# Power.net
KiCad netlist of a schematic drawn in Altium Designer
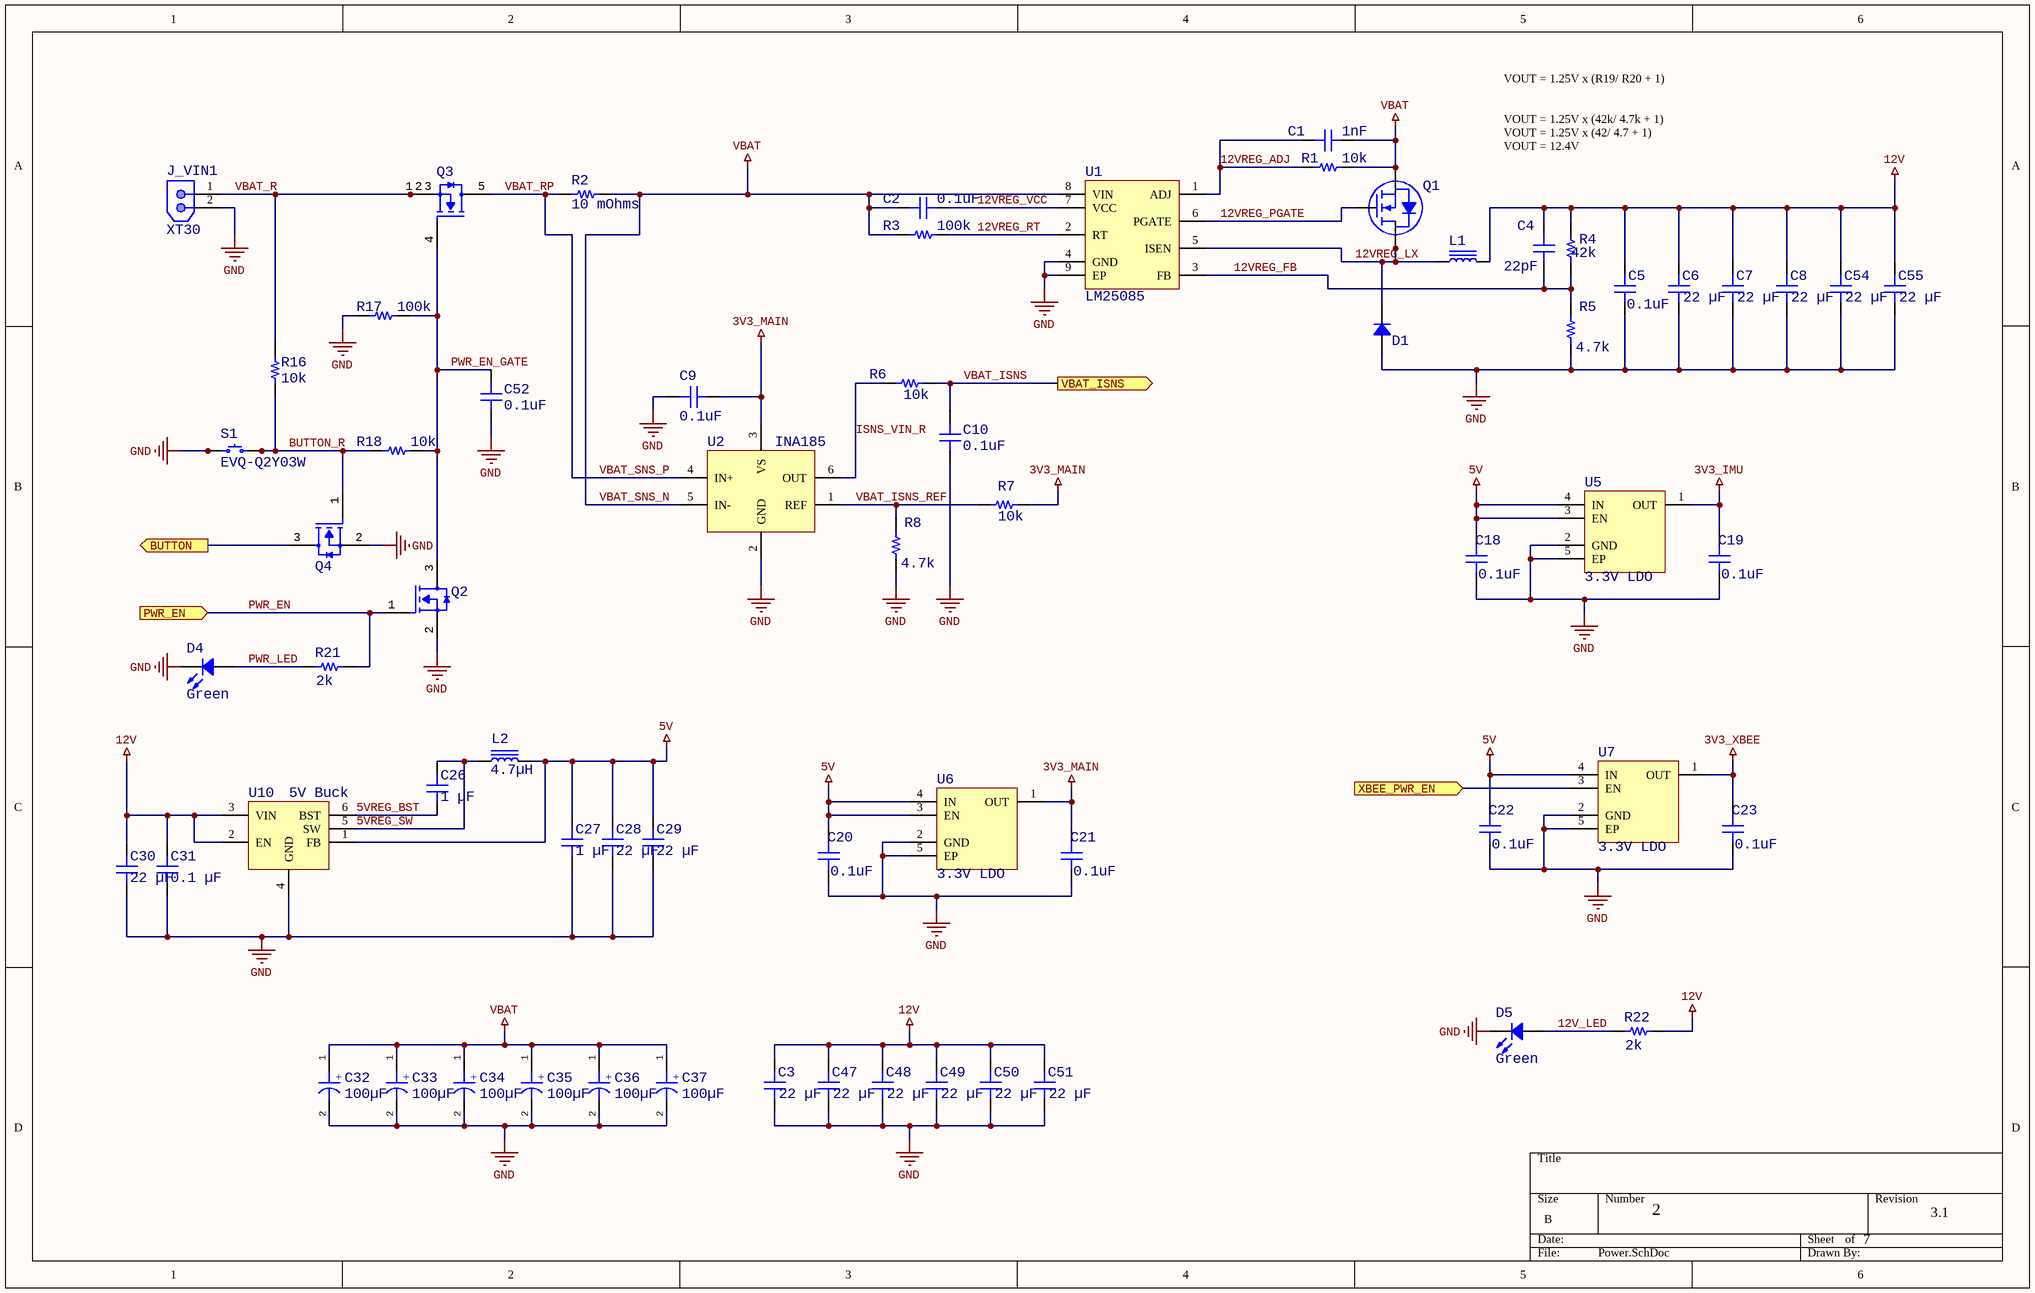
[diagram p0: Power.SchDoc]

(export (version "E")
  (design (tool "Eeschema 10.0.6"))
  (components
    (comp (ref "C1")
      (value "1nF")
      (footprint "CAP_0402")
      (description "CAP CER 402")
      (libsource (lib "IC") (part "CAP_0402"))
    )
    (comp (ref "C2")
      (value "0.1uF")
      (footprint "CAP_0402")
      (description "CAP CER 402")
      (libsource (lib "IC") (part "CAP_0402"))
    )
    (comp (ref "C3")
      (value "22 µF")
      (footprint "CAP 0805_2012")
      (description "CAP CER 22UF 16V X6S 0805")
      (fields (field (name "PART NUMBER") "KGM21AS61C226MU") (field (name "MANUFACTURER") "KYOCERA AVX"))
      (libsource (lib "Celestial Altium Library - altium_library") (part "Capacitor"))
    )
    (comp (ref "C4")
      (value "22pF")
      (footprint "CAP_0402")
      (description "CAP CER 402")
      (libsource (lib "IC") (part "CAP_0402"))
    )
    (comp (ref "C5")
      (value "0.1uF")
      (footprint "CAP_0402")
      (description "CAP CER 402")
      (libsource (lib "IC") (part "CAP_0402"))
    )
    (comp (ref "C6")
      (value "22 µF")
      (footprint "CAP 0805_2012")
      (description "CAP CER 22UF 16V X6S 0805")
      (fields (field (name "PART NUMBER") "KGM21AS61C226MU") (field (name "MANUFACTURER") "KYOCERA AVX"))
      (libsource (lib "Celestial Altium Library - altium_library") (part "Capacitor"))
    )
    (comp (ref "C7")
      (value "22 µF")
      (footprint "CAP 0805_2012")
      (description "CAP CER 22UF 16V X6S 0805")
      (fields (field (name "PART NUMBER") "KGM21AS61C226MU") (field (name "MANUFACTURER") "KYOCERA AVX"))
      (libsource (lib "Celestial Altium Library - altium_library") (part "Capacitor"))
    )
    (comp (ref "C8")
      (value "22 µF")
      (footprint "CAP 0805_2012")
      (description "CAP CER 22UF 16V X6S 0805")
      (fields (field (name "PART NUMBER") "KGM21AS61C226MU") (field (name "MANUFACTURER") "KYOCERA AVX"))
      (libsource (lib "Celestial Altium Library - altium_library") (part "Capacitor"))
    )
    (comp (ref "C9")
      (value "0.1uF")
      (footprint "CAP_0402")
      (description "CAP CER 402")
      (libsource (lib "IC") (part "CAP_0402"))
    )
    (comp (ref "C10")
      (value "0.1uF")
      (footprint "CAP_0402")
      (description "CAP CER 402")
      (libsource (lib "IC") (part "CAP_0402"))
    )
    (comp (ref "C18")
      (value "0.1uF")
      (footprint "CAP_0402")
      (description "CAP CER 402")
      (libsource (lib "IC") (part "CAP_0402"))
    )
    (comp (ref "C19")
      (value "0.1uF")
      (footprint "CAP_0402")
      (description "CAP CER 402")
      (libsource (lib "IC") (part "CAP_0402"))
    )
    (comp (ref "C20")
      (value "0.1uF")
      (footprint "CAP_0402")
      (description "CAP CER 402")
      (libsource (lib "IC") (part "CAP_0402"))
    )
    (comp (ref "C21")
      (value "0.1uF")
      (footprint "CAP_0402")
      (description "CAP CER 402")
      (libsource (lib "IC") (part "CAP_0402"))
    )
    (comp (ref "C22")
      (value "0.1uF")
      (footprint "CAP_0402")
      (description "CAP CER 402")
      (libsource (lib "IC") (part "CAP_0402"))
    )
    (comp (ref "C23")
      (value "0.1uF")
      (footprint "CAP_0402")
      (description "CAP CER 402")
      (libsource (lib "IC") (part "CAP_0402"))
    )
    (comp (ref "C26")
      (value "1 µF")
      (footprint "CAP 0402_1005")
      (description "CAP CER 0.1UF 16V X7R 0402")
      (fields (field (name "PART NUMBER") "C0402C104K4RACAUTO") (field (name "MANUFACTURER") "KEMET"))
      (libsource (lib "Celestial Altium Library - altium_library") (part "Capacitor"))
    )
    (comp (ref "C27")
      (value "1 µF")
      (footprint "CAP 0402_1005")
      (description "CAP CER 0.1UF 16V X7R 0402")
      (fields (field (name "PART NUMBER") "C0402C104K4RACAUTO") (field (name "MANUFACTURER") "KEMET"))
      (libsource (lib "Celestial Altium Library - altium_library") (part "Capacitor"))
    )
    (comp (ref "C28")
      (value "22 µF")
      (footprint "CAP 0603_1608")
      (description "CAP CER 47UF 6.3V X5R 0603")
      (fields
        (field (name "PART NUMBER") "C0603B476M007T")
        (field (name "MANUFACTURER") "Holy Stone Enterprise Co., Ltd.")
      )
      (libsource (lib "Celestial Altium Library - altium_library") (part "Capacitor"))
    )
    (comp (ref "C29")
      (value "22 µF")
      (footprint "CAP 0603_1608")
      (description "CAP CER 47UF 6.3V X5R 0603")
      (fields
        (field (name "PART NUMBER") "C0603B476M007T")
        (field (name "MANUFACTURER") "Holy Stone Enterprise Co., Ltd.")
      )
      (libsource (lib "Celestial Altium Library - altium_library") (part "Capacitor"))
    )
    (comp (ref "C30")
      (value "22 µF")
      (footprint "CAP 0603_1608")
      (description "CAP CER 47UF 6.3V X5R 0603")
      (fields
        (field (name "PART NUMBER") "C0603B476M007T")
        (field (name "MANUFACTURER") "Holy Stone Enterprise Co., Ltd.")
      )
      (libsource (lib "Celestial Altium Library - altium_library") (part "Capacitor"))
    )
    (comp (ref "C31")
      (value "0.1 µF")
      (footprint "CAP 0402_1005")
      (description "CAP CER 0.1UF 16V X7R 0402")
      (fields (field (name "PART NUMBER") "C0402C104K4RACAUTO") (field (name "MANUFACTURER") "KEMET"))
      (libsource (lib "Celestial Altium Library - altium_library") (part "Capacitor"))
    )
    (comp (ref "C32")
      (value "100µF")
      (footprint "UWZ1V101MCL1GS")
      (fields (field (name "Comment") "UWZ1V101MCL1GS"))
      (libsource (lib "Raise Robotics") (part "Polarized Capacitor Pin1+"))
    )
    (comp (ref "C33")
      (value "100µF")
      (footprint "UWZ1V101MCL1GS")
      (fields (field (name "Comment") "UWZ1V101MCL1GS"))
      (libsource (lib "Raise Robotics") (part "Polarized Capacitor Pin1+"))
    )
    (comp (ref "C34")
      (value "100µF")
      (footprint "UWZ1V101MCL1GS")
      (fields (field (name "Comment") "UWZ1V101MCL1GS"))
      (libsource (lib "Raise Robotics") (part "Polarized Capacitor Pin1+"))
    )
    (comp (ref "C35")
      (value "100µF")
      (footprint "UWZ1V101MCL1GS")
      (fields (field (name "Comment") "UWZ1V101MCL1GS"))
      (libsource (lib "Raise Robotics") (part "Polarized Capacitor Pin1+"))
    )
    (comp (ref "C36")
      (value "100µF")
      (footprint "UWZ1V101MCL1GS")
      (fields (field (name "Comment") "UWZ1V101MCL1GS"))
      (libsource (lib "Raise Robotics") (part "Polarized Capacitor Pin1+"))
    )
    (comp (ref "C37")
      (value "100µF")
      (footprint "UWZ1V101MCL1GS")
      (fields (field (name "Comment") "UWZ1V101MCL1GS"))
      (libsource (lib "Raise Robotics") (part "Polarized Capacitor Pin1+"))
    )
    (comp (ref "C47")
      (value "22 µF")
      (footprint "CAP 0805_2012")
      (description "CAP CER 22UF 16V X6S 0805")
      (fields (field (name "PART NUMBER") "KGM21AS61C226MU") (field (name "MANUFACTURER") "KYOCERA AVX"))
      (libsource (lib "Celestial Altium Library - altium_library") (part "Capacitor"))
    )
    (comp (ref "C48")
      (value "22 µF")
      (footprint "CAP 0805_2012")
      (description "CAP CER 22UF 16V X6S 0805")
      (fields (field (name "PART NUMBER") "KGM21AS61C226MU") (field (name "MANUFACTURER") "KYOCERA AVX"))
      (libsource (lib "Celestial Altium Library - altium_library") (part "Capacitor"))
    )
    (comp (ref "C49")
      (value "22 µF")
      (footprint "CAP 0805_2012")
      (description "CAP CER 22UF 16V X6S 0805")
      (fields (field (name "PART NUMBER") "KGM21AS61C226MU") (field (name "MANUFACTURER") "KYOCERA AVX"))
      (libsource (lib "Celestial Altium Library - altium_library") (part "Capacitor"))
    )
    (comp (ref "C50")
      (value "22 µF")
      (footprint "CAP 0805_2012")
      (description "CAP CER 22UF 16V X6S 0805")
      (fields (field (name "PART NUMBER") "KGM21AS61C226MU") (field (name "MANUFACTURER") "KYOCERA AVX"))
      (libsource (lib "Celestial Altium Library - altium_library") (part "Capacitor"))
    )
    (comp (ref "C51")
      (value "22 µF")
      (footprint "CAP 0805_2012")
      (description "CAP CER 22UF 16V X6S 0805")
      (fields (field (name "PART NUMBER") "KGM21AS61C226MU") (field (name "MANUFACTURER") "KYOCERA AVX"))
      (libsource (lib "Celestial Altium Library - altium_library") (part "Capacitor"))
    )
    (comp (ref "C52")
      (value "0.1uF")
      (footprint "CAP_0402")
      (description "CAP CER 402")
      (libsource (lib "IC") (part "CAP_0402"))
    )
    (comp (ref "C54")
      (value "22 µF")
      (footprint "CAP 0805_2012")
      (description "CAP CER 22UF 16V X6S 0805")
      (fields (field (name "PART NUMBER") "KGM21AS61C226MU") (field (name "MANUFACTURER") "KYOCERA AVX"))
      (libsource (lib "Celestial Altium Library - altium_library") (part "Capacitor"))
    )
    (comp (ref "C55")
      (value "22 µF")
      (footprint "CAP 0805_2012")
      (description "CAP CER 22UF 16V X6S 0805")
      (fields (field (name "PART NUMBER") "KGM21AS61C226MU") (field (name "MANUFACTURER") "KYOCERA AVX"))
      (libsource (lib "Celestial Altium Library - altium_library") (part "Capacitor"))
    )
    (comp (ref "D1")
      (value "SE10FGHM3/H")
      (footprint "SMF DO-219AB")
      (description "DIODE GEN PURP 400V 1A DO219AB")
      (fields (field (name "MANUFACTURER") "Vishay Semiconductor Diodes Division"))
      (libsource (lib "Celestial Altium Library - altium_library") (part "Diode"))
    )
    (comp (ref "D4")
      (value "Green")
      (footprint "LED 0603_1608 GREEN")
      (description "LED GREEN CLEAR 2SMD")
      (fields (field (name "PART NUMBER") "XZCDGK53W-8VF") (field (name "MANUFACTURER") "SunLED"))
      (libsource (lib "Celestial Altium Library - altium_library") (part "LED"))
    )
    (comp (ref "D5")
      (value "Green")
      (footprint "LED 0603_1608 GREEN")
      (description "LED GREEN CLEAR 2SMD")
      (fields (field (name "PART NUMBER") "XZCDGK53W-8VF") (field (name "MANUFACTURER") "SunLED"))
      (libsource (lib "Celestial Altium Library - altium_library") (part "LED"))
    )
    (comp (ref "J_VIN1") (value "XT30") (footprint "XT30") (libsource (lib "IC") (part "XT30")))
    (comp (ref "L1")
      (value "MPL-AL5050-5R6")
      (footprint "MPL-AL5050-5R6")
      (description "FIXED IND 5.6UH 6.8A 20 MOHM SMD")
      (fields (field (name "MF") "Laird-Signal Integrity Products") (field (name "MP") "MGV05021R0M-10"))
      (libsource (lib "IC") (part "MPL-AL5050-5R6"))
    )
    (comp (ref "L2")
      (value "4.7µH")
      (footprint "IND 1008_2520")
      (description "FIXED IND 4.7UH 1A 110 MOHM SMD")
      (fields (field (name "PART NUMBER") "MLP2520S4R7ST0S1") (field (name "MANUFACTURER") "TDK Corporation"))
      (libsource (lib "Celestial Altium Library - altium_library") (part "Inductor"))
    )
    (comp (ref "Q1")
      (value "NVTFS5C680NL")
      (footprint "NVTFS015N04CTAG")
      (description "N-FET")
      (libsource (lib "IC") (part "NVTFS5C680NL"))
    )
    (comp (ref "Q2")
      (value "DMN61D9UWQ-7")
      (footprint "DMN61D9UWQ-7")
      (description "Small Signal Field-Effect Transistor")
      (libsource (lib "Raise Robotics") (part "n-FET 3 pin SOT"))
    )
    (comp (ref "Q3")
      (value "STL220N6F7")
      (footprint "STL220N6F7")
      (fields (field (name "POWER") "4.8W"))
      (libsource (lib "Raise Robotics") (part "LFPAK56, Power-SO8"))
    )
    (comp (ref "Q4")
      (value "DMN61D9UWQ-7")
      (footprint "DMN61D9UWQ-7")
      (description "Small Signal Field-Effect Transistor")
      (libsource (lib "Raise Robotics") (part "n-FET 3 pin SOT"))
    )
    (comp (ref "R1")
      (value "10k")
      (footprint "RES_0402")
      (description "RES 0402")
      (libsource (lib "IC") (part "RES_0402"))
    )
    (comp (ref "R2")
      (value "10 mOhms")
      (footprint "RES 1206_3216")
      (description "RES 0.039 OHM 1% 3/4W 1206")
      (fields (field (name "PART NUMBER") "KRL1632E-M-R039-F-T5") (field (name "MANUFACTURER") "Susumu"))
      (libsource (lib "Celestial Altium Library - altium_library") (part "Resistor"))
    )
    (comp (ref "R3")
      (value "100k")
      (footprint "RES_0402")
      (description "RES 0402")
      (libsource (lib "IC") (part "RES_0402"))
    )
    (comp (ref "R4")
      (value "42k")
      (footprint "RES_0402")
      (description "RES 0402")
      (libsource (lib "IC") (part "RES_0402"))
    )
    (comp (ref "R5")
      (value "4.7k")
      (footprint "RES_0402")
      (description "RES 0402")
      (libsource (lib "IC") (part "RES_0402"))
    )
    (comp (ref "R6")
      (value "10k")
      (footprint "RES_0402")
      (description "RES 0402")
      (libsource (lib "IC") (part "RES_0402"))
    )
    (comp (ref "R7")
      (value "10k")
      (footprint "RES_0402")
      (description "RES 0402")
      (libsource (lib "IC") (part "RES_0402"))
    )
    (comp (ref "R8")
      (value "4.7k")
      (footprint "RES_0402")
      (description "RES 0402")
      (libsource (lib "IC") (part "RES_0402"))
    )
    (comp (ref "R16")
      (value "10k")
      (footprint "RES_0402")
      (description "RES 0402")
      (libsource (lib "IC") (part "RES_0402"))
    )
    (comp (ref "R17")
      (value "100k")
      (footprint "RES_0402")
      (description "RES 0402")
      (libsource (lib "IC") (part "RES_0402"))
    )
    (comp (ref "R18")
      (value "10k")
      (footprint "RES_0402")
      (description "RES 0402")
      (libsource (lib "IC") (part "RES_0402"))
    )
    (comp (ref "R21")
      (value "2k")
      (footprint "RES_0402")
      (description "RES 0402")
      (libsource (lib "IC") (part "RES_0402"))
    )
    (comp (ref "R22")
      (value "2k")
      (footprint "RES_0402")
      (description "RES 0402")
      (libsource (lib "IC") (part "RES_0402"))
    )
    (comp (ref "S1")
      (value "EVQ-Q2Y03W")
      (footprint "PANASONIC EVQQ2")
      (description "SWITCH TACTILE SPST-NO 0.02A 15V")
      (fields (field (name "MANUFACTURER") "Panasonic Electronic Components"))
      (libsource (lib "Celestial Altium Library - altium_library") (part "SPST-NO 4 PIN"))
    )
    (comp (ref "U1")
      (value "LM25085")
      (footprint "8-WSON_3x3_0.5mm")
      (description "PFET Buck Controller")
      (libsource (lib "IC") (part "LM25085"))
    )
    (comp (ref "U2")
      (value "INA185")
      (footprint "TI SC70-6 DCK")
      (description "INA185A2")
      (libsource (lib "IC") (part "INA185"))
    )
    (comp (ref "U5") (value "3.3V LDO") (footprint "XDFN-4") (libsource (lib "IC") (part "TLV74033PDQNR")))
    (comp (ref "U6") (value "3.3V LDO") (footprint "XDFN-4") (libsource (lib "IC") (part "TLV74033PDQNR")))
    (comp (ref "U7") (value "3.3V LDO") (footprint "XDFN-4") (libsource (lib "IC") (part "TLV74033PDQNR")))
    (comp (ref "U10")
      (value "5V Buck")
      (footprint "TSOT-26-6 - 3.2mm")
      (description "5V fixed step down Buck")
      (libsource (lib "IC") (part "AP63205WU-7"))
    )
  )
  (nets
    (net (code "1") (name "/5VREG_BST") (class "Default")
      (node (ref "C26") (pin "1") (pinfunction "1_1") (pintype "passive"))
      (node (ref "U10") (pin "6") (pinfunction "BST_6") (pintype "passive"))
    )
    (net (code "2") (name "/5VREG_SW") (class "Default")
      (node (ref "C26") (pin "2") (pinfunction "2_2") (pintype "passive"))
      (node (ref "L2") (pin "1") (pinfunction "1_1") (pintype "passive"))
      (node (ref "U10") (pin "5") (pinfunction "SW_5") (pintype "passive"))
    )
    (net (code "3") (name "/12VREG_ADJ") (class "Default")
      (node (ref "C1") (pin "1") (pinfunction "1_1") (pintype "passive"))
      (node (ref "R1") (pin "2") (pinfunction "2_2") (pintype "passive"))
      (node (ref "U1") (pin "1") (pinfunction "ADJ_1") (pintype "passive"))
    )
    (net (code "4") (name "/12VREG_FB") (class "Default")
      (node (ref "C4") (pin "1") (pinfunction "1_1") (pintype "passive"))
      (node (ref "R4") (pin "2") (pinfunction "2_2") (pintype "passive"))
      (node (ref "R5") (pin "1") (pinfunction "1_1") (pintype "passive"))
      (node (ref "U1") (pin "3") (pinfunction "FB_3") (pintype "passive"))
    )
    (net (code "5") (name "/12VREG_LX") (class "Default")
      (node (ref "D1") (pin "2") (pinfunction "2_2") (pintype "passive"))
      (node (ref "L1") (pin "1") (pinfunction "1_1") (pintype "passive"))
      (node (ref "Q1") (pin "5") (pinfunction "D_5") (pintype "passive"))
      (node (ref "Q1") (pin "6") (pinfunction "D_6") (pintype "passive"))
      (node (ref "Q1") (pin "7") (pinfunction "D_7") (pintype "passive"))
      (node (ref "Q1") (pin "8") (pinfunction "D_8") (pintype "passive"))
      (node (ref "U1") (pin "5") (pinfunction "ISEN_5") (pintype "passive"))
    )
    (net (code "6") (name "/12VREG_PGATE") (class "Default")
      (node (ref "Q1") (pin "4") (pinfunction "G_4") (pintype "passive"))
      (node (ref "U1") (pin "6") (pinfunction "PGATE_6") (pintype "passive"))
    )
    (net (code "7") (name "/12VREG_RT") (class "Default")
      (node (ref "R3") (pin "1") (pinfunction "1_1") (pintype "passive"))
      (node (ref "U1") (pin "2") (pinfunction "RT_2") (pintype "passive"))
    )
    (net (code "8") (name "/12VREG_VCC") (class "Default")
      (node (ref "C2") (pin "2") (pinfunction "2_2") (pintype "passive"))
      (node (ref "U1") (pin "7") (pinfunction "VCC_7") (pintype "passive"))
    )
    (net (code "9") (name "/12V_LED") (class "Default")
      (node (ref "D5") (pin "1") (pinfunction "1_1") (pintype "passive"))
      (node (ref "R22") (pin "1") (pinfunction "1_1") (pintype "passive"))
    )
    (net (code "10") (name "/BUTTON") (class "Default")
      (node (ref "Q4") (pin "3") (pinfunction "DRAIN_3") (pintype "passive"))
    )
    (net (code "11") (name "/BUTTON_R") (class "Default")
      (node (ref "Q4") (pin "1") (pinfunction "GATE_1") (pintype "passive"))
      (node (ref "R16") (pin "2") (pinfunction "2_2") (pintype "passive"))
      (node (ref "R18") (pin "2") (pinfunction "2_2") (pintype "passive"))
      (node (ref "S1") (pin "3") (pinfunction "3_3") (pintype "passive"))
      (node (ref "S1") (pin "4") (pinfunction "4_4") (pintype "passive"))
    )
    (net (code "12") (name "/ISNS_VIN_R") (class "Default")
      (node (ref "R6") (pin "2") (pinfunction "2_2") (pintype "passive"))
      (node (ref "U2") (pin "6") (pinfunction "OUT_6") (pintype "passive"))
    )
    (net (code "13") (name "/PWR_EN") (class "Default")
      (node (ref "Q2") (pin "1") (pinfunction "GATE_1") (pintype "passive"))
      (node (ref "R21") (pin "2") (pinfunction "2_2") (pintype "passive"))
    )
    (net (code "14") (name "/PWR_EN_GATE") (class "Default")
      (node (ref "C52") (pin "1") (pinfunction "1_1") (pintype "passive"))
      (node (ref "Q2") (pin "3") (pinfunction "DRAIN_3") (pintype "passive"))
      (node (ref "Q3") (pin "4") (pinfunction "GATE_4") (pintype "passive"))
      (node (ref "R17") (pin "1") (pinfunction "1_1") (pintype "passive"))
      (node (ref "R18") (pin "1") (pinfunction "1_1") (pintype "passive"))
    )
    (net (code "15") (name "/PWR_LED") (class "Default")
      (node (ref "D4") (pin "1") (pinfunction "1_1") (pintype "passive"))
      (node (ref "R21") (pin "1") (pinfunction "1_1") (pintype "passive"))
    )
    (net (code "16") (name "/VBAT_ISNS") (class "Default")
      (node (ref "C10") (pin "1") (pinfunction "1_1") (pintype "passive"))
      (node (ref "R6") (pin "1") (pinfunction "1_1") (pintype "passive"))
    )
    (net (code "17") (name "/VBAT_ISNS_REF") (class "Default")
      (node (ref "R7") (pin "2") (pinfunction "2_2") (pintype "passive"))
      (node (ref "R8") (pin "1") (pinfunction "1_1") (pintype "passive"))
      (node (ref "U2") (pin "1") (pinfunction "REF_1") (pintype "passive"))
    )
    (net (code "18") (name "/VBAT_R") (class "Default")
      (node (ref "J_VIN1") (pin "1") (pinfunction "1_1") (pintype "passive"))
      (node (ref "Q3") (pin "1") (pinfunction "SOURCE_1") (pintype "passive"))
      (node (ref "Q3") (pin "2") (pinfunction "SOURCE_2") (pintype "passive"))
      (node (ref "Q3") (pin "3") (pinfunction "SOURCE_3") (pintype "passive"))
      (node (ref "R16") (pin "1") (pinfunction "1_1") (pintype "passive"))
    )
    (net (code "19") (name "/VBAT_RP") (class "Default")
      (node (ref "Q3") (pin "5") (pinfunction "DRAIN_5") (pintype "passive"))
      (node (ref "R2") (pin "1") (pinfunction "1_1") (pintype "passive"))
      (node (ref "U2") (pin "4") (pinfunction "IN+_4") (pintype "passive"))
    )
    (net (code "20") (name "/XBEE_PWR_EN") (class "Default")
      (node (ref "U7") (pin "3") (pinfunction "EN_3") (pintype "passive"))
    )
    (net (code "21") (name "3V3_IMU") (class "Default")
      (node (ref "C19") (pin "2") (pinfunction "2_2") (pintype "passive"))
      (node (ref "U5") (pin "1") (pinfunction "OUT_1") (pintype "passive"))
    )
    (net (code "22") (name "3V3_MAIN") (class "Default")
      (node (ref "C21") (pin "2") (pinfunction "2_2") (pintype "passive"))
      (node (ref "C9") (pin "1") (pinfunction "1_1") (pintype "passive"))
      (node (ref "R7") (pin "1") (pinfunction "1_1") (pintype "passive"))
      (node (ref "U2") (pin "3") (pinfunction "VS_3") (pintype "passive"))
      (node (ref "U6") (pin "1") (pinfunction "OUT_1") (pintype "passive"))
    )
    (net (code "23") (name "3V3_XBEE") (class "Default")
      (node (ref "C23") (pin "2") (pinfunction "2_2") (pintype "passive"))
      (node (ref "U7") (pin "1") (pinfunction "OUT_1") (pintype "passive"))
    )
    (net (code "24") (name "5V") (class "Default")
      (node (ref "C18") (pin "2") (pinfunction "2_2") (pintype "passive"))
      (node (ref "C20") (pin "2") (pinfunction "2_2") (pintype "passive"))
      (node (ref "C22") (pin "2") (pinfunction "2_2") (pintype "passive"))
      (node (ref "C27") (pin "2") (pinfunction "2_2") (pintype "passive"))
      (node (ref "C28") (pin "2") (pinfunction "2_2") (pintype "passive"))
      (node (ref "C29") (pin "2") (pinfunction "2_2") (pintype "passive"))
      (node (ref "L2") (pin "2") (pinfunction "2_2") (pintype "passive"))
      (node (ref "U10") (pin "1") (pinfunction "FB_1") (pintype "passive"))
      (node (ref "U5") (pin "3") (pinfunction "EN_3") (pintype "passive"))
      (node (ref "U5") (pin "4") (pinfunction "IN_4") (pintype "passive"))
      (node (ref "U6") (pin "3") (pinfunction "EN_3") (pintype "passive"))
      (node (ref "U6") (pin "4") (pinfunction "IN_4") (pintype "passive"))
      (node (ref "U7") (pin "4") (pinfunction "IN_4") (pintype "passive"))
    )
    (net (code "25") (name "12V") (class "Default")
      (node (ref "C3") (pin "2") (pinfunction "2_2") (pintype "passive"))
      (node (ref "C30") (pin "2") (pinfunction "2_2") (pintype "passive"))
      (node (ref "C31") (pin "2") (pinfunction "2_2") (pintype "passive"))
      (node (ref "C4") (pin "2") (pinfunction "2_2") (pintype "passive"))
      (node (ref "C47") (pin "2") (pinfunction "2_2") (pintype "passive"))
      (node (ref "C48") (pin "2") (pinfunction "2_2") (pintype "passive"))
      (node (ref "C49") (pin "2") (pinfunction "2_2") (pintype "passive"))
      (node (ref "C5") (pin "2") (pinfunction "2_2") (pintype "passive"))
      (node (ref "C50") (pin "2") (pinfunction "2_2") (pintype "passive"))
      (node (ref "C51") (pin "2") (pinfunction "2_2") (pintype "passive"))
      (node (ref "C54") (pin "2") (pinfunction "2_2") (pintype "passive"))
      (node (ref "C55") (pin "2") (pinfunction "2_2") (pintype "passive"))
      (node (ref "C6") (pin "2") (pinfunction "2_2") (pintype "passive"))
      (node (ref "C7") (pin "2") (pinfunction "2_2") (pintype "passive"))
      (node (ref "C8") (pin "2") (pinfunction "2_2") (pintype "passive"))
      (node (ref "L1") (pin "2") (pinfunction "2_2") (pintype "passive"))
      (node (ref "R22") (pin "2") (pinfunction "2_2") (pintype "passive"))
      (node (ref "R4") (pin "1") (pinfunction "1_1") (pintype "passive"))
      (node (ref "U10") (pin "2") (pinfunction "EN_2") (pintype "passive"))
      (node (ref "U10") (pin "3") (pinfunction "VIN_3") (pintype "passive"))
    )
    (net (code "26") (name "GND") (class "Default")
      (node (ref "C10") (pin "2") (pinfunction "2_2") (pintype "passive"))
      (node (ref "C18") (pin "1") (pinfunction "1_1") (pintype "passive"))
      (node (ref "C19") (pin "1") (pinfunction "1_1") (pintype "passive"))
      (node (ref "C20") (pin "1") (pinfunction "1_1") (pintype "passive"))
      (node (ref "C21") (pin "1") (pinfunction "1_1") (pintype "passive"))
      (node (ref "C22") (pin "1") (pinfunction "1_1") (pintype "passive"))
      (node (ref "C23") (pin "1") (pinfunction "1_1") (pintype "passive"))
      (node (ref "C27") (pin "1") (pinfunction "1_1") (pintype "passive"))
      (node (ref "C28") (pin "1") (pinfunction "1_1") (pintype "passive"))
      (node (ref "C29") (pin "1") (pinfunction "1_1") (pintype "passive"))
      (node (ref "C3") (pin "1") (pinfunction "1_1") (pintype "passive"))
      (node (ref "C30") (pin "1") (pinfunction "1_1") (pintype "passive"))
      (node (ref "C31") (pin "1") (pinfunction "1_1") (pintype "passive"))
      (node (ref "C32") (pin "2") (pinfunction "2_2") (pintype "passive"))
      (node (ref "C33") (pin "2") (pinfunction "2_2") (pintype "passive"))
      (node (ref "C34") (pin "2") (pinfunction "2_2") (pintype "passive"))
      (node (ref "C35") (pin "2") (pinfunction "2_2") (pintype "passive"))
      (node (ref "C36") (pin "2") (pinfunction "2_2") (pintype "passive"))
      (node (ref "C37") (pin "2") (pinfunction "2_2") (pintype "passive"))
      (node (ref "C47") (pin "1") (pinfunction "1_1") (pintype "passive"))
      (node (ref "C48") (pin "1") (pinfunction "1_1") (pintype "passive"))
      (node (ref "C49") (pin "1") (pinfunction "1_1") (pintype "passive"))
      (node (ref "C5") (pin "1") (pinfunction "1_1") (pintype "passive"))
      (node (ref "C50") (pin "1") (pinfunction "1_1") (pintype "passive"))
      (node (ref "C51") (pin "1") (pinfunction "1_1") (pintype "passive"))
      (node (ref "C52") (pin "2") (pinfunction "2_2") (pintype "passive"))
      (node (ref "C54") (pin "1") (pinfunction "1_1") (pintype "passive"))
      (node (ref "C55") (pin "1") (pinfunction "1_1") (pintype "passive"))
      (node (ref "C6") (pin "1") (pinfunction "1_1") (pintype "passive"))
      (node (ref "C7") (pin "1") (pinfunction "1_1") (pintype "passive"))
      (node (ref "C8") (pin "1") (pinfunction "1_1") (pintype "passive"))
      (node (ref "C9") (pin "2") (pinfunction "2_2") (pintype "passive"))
      (node (ref "D1") (pin "1") (pinfunction "1_1") (pintype "passive"))
      (node (ref "D4") (pin "2") (pinfunction "2_2") (pintype "passive"))
      (node (ref "D5") (pin "2") (pinfunction "2_2") (pintype "passive"))
      (node (ref "J_VIN1") (pin "2") (pinfunction "2_2") (pintype "passive"))
      (node (ref "Q2") (pin "2") (pinfunction "SOURCE_2") (pintype "passive"))
      (node (ref "Q4") (pin "2") (pinfunction "SOURCE_2") (pintype "passive"))
      (node (ref "R17") (pin "2") (pinfunction "2_2") (pintype "passive"))
      (node (ref "R5") (pin "2") (pinfunction "2_2") (pintype "passive"))
      (node (ref "R8") (pin "2") (pinfunction "2_2") (pintype "passive"))
      (node (ref "S1") (pin "1") (pinfunction "1_1") (pintype "passive"))
      (node (ref "S1") (pin "2") (pinfunction "2_2") (pintype "passive"))
      (node (ref "U1") (pin "4") (pinfunction "GND_4") (pintype "passive"))
      (node (ref "U1") (pin "9") (pinfunction "EP_9") (pintype "passive"))
      (node (ref "U10") (pin "4") (pinfunction "GND_4") (pintype "passive"))
      (node (ref "U2") (pin "2") (pinfunction "GND_2") (pintype "passive"))
      (node (ref "U5") (pin "2") (pinfunction "GND_2") (pintype "passive"))
      (node (ref "U5") (pin "5") (pinfunction "EP_5") (pintype "passive"))
      (node (ref "U6") (pin "2") (pinfunction "GND_2") (pintype "passive"))
      (node (ref "U6") (pin "5") (pinfunction "EP_5") (pintype "passive"))
      (node (ref "U7") (pin "2") (pinfunction "GND_2") (pintype "passive"))
      (node (ref "U7") (pin "5") (pinfunction "EP_5") (pintype "passive"))
    )
    (net (code "27") (name "VBAT") (class "Default")
      (node (ref "C1") (pin "2") (pinfunction "2_2") (pintype "passive"))
      (node (ref "C2") (pin "1") (pinfunction "1_1") (pintype "passive"))
      (node (ref "C32") (pin "1") (pinfunction "1_1") (pintype "passive"))
      (node (ref "C33") (pin "1") (pinfunction "1_1") (pintype "passive"))
      (node (ref "C34") (pin "1") (pinfunction "1_1") (pintype "passive"))
      (node (ref "C35") (pin "1") (pinfunction "1_1") (pintype "passive"))
      (node (ref "C36") (pin "1") (pinfunction "1_1") (pintype "passive"))
      (node (ref "C37") (pin "1") (pinfunction "1_1") (pintype "passive"))
      (node (ref "Q1") (pin "1") (pinfunction "S_1") (pintype "passive"))
      (node (ref "Q1") (pin "2") (pinfunction "S_2") (pintype "passive"))
      (node (ref "Q1") (pin "3") (pinfunction "S_3") (pintype "passive"))
      (node (ref "R1") (pin "1") (pinfunction "1_1") (pintype "passive"))
      (node (ref "R2") (pin "2") (pinfunction "2_2") (pintype "passive"))
      (node (ref "R3") (pin "2") (pinfunction "2_2") (pintype "passive"))
      (node (ref "U1") (pin "8") (pinfunction "VIN_8") (pintype "passive"))
      (node (ref "U2") (pin "5") (pinfunction "IN-_5") (pintype "passive"))
    )
  )
)
